# Power_Supply.net
KiCad netlist of a schematic drawn in Altium Designer
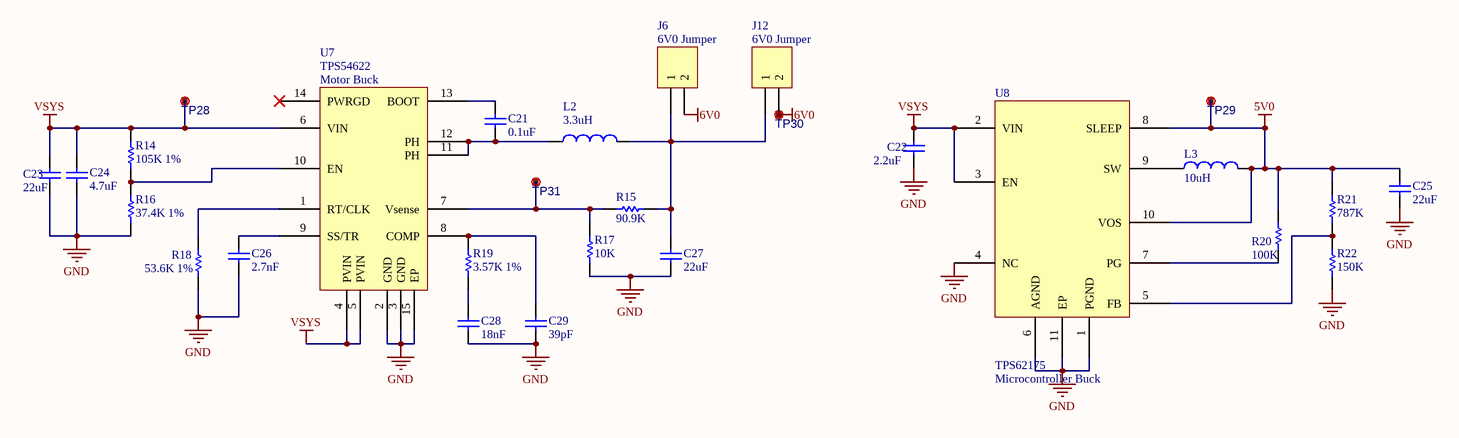
[diagram p0: Power_Supply.SchDoc]

(export (version "E")
  (design (tool "Eeschema 10.0.6"))
  (components
    (comp (ref "C21")
      (value "0.1uF")
      (footprint "CAPC0805(2012)145_N")
      (description "CAP CER 0.1UF 25V X7R 0805")
      (fields (field (name "TOLERANCE") "Â±10%"))
      (libsource (lib "Altium Content Vault") (part "CMP-1036-04410-1"))
    )
    (comp (ref "C22")
      (value "2.2uF")
      (footprint "CAPC0603(1608)100_N")
      (description "CAP CER 2.2UF 16V X5R 0603")
      (fields (field (name "TOLERANCE") "Â±10%"))
      (libsource (lib "Altium Content Vault") (part "CMP-1035-02763-1"))
    )
    (comp (ref "C23")
      (value "22uF")
      (footprint "CAPC1206(3216)190_N")
      (description "CAP CER 22UF 16V X5R 1206")
      (fields (field (name "TOLERANCE") "Â±20%"))
      (libsource (lib "Altium Content Vault") (part "CMP-1037-04993-1"))
    )
    (comp (ref "C24")
      (value "4.7uF")
      (footprint "CAPC0805(2012)145_N")
      (description "CAP CER 4.7UF 25V X5R 0805")
      (fields (field (name "TOLERANCE") "Â±10%"))
      (libsource (lib "Altium Content Vault") (part "CMP-1036-04895-1"))
    )
    (comp (ref "C25")
      (value "22uF")
      (footprint "CAPC0805(2012)145_N")
      (description "CAP CER 22UF 6.3V X5R 0805")
      (fields (field (name "TOLERANCE") "Â±20%"))
      (libsource (lib "Altium Content Vault") (part "CMP-1036-04939-1"))
    )
    (comp (ref "C26")
      (value "2.7nF")
      (footprint "CAPC0805(2012)145_N")
      (description "CAP CER 2700PF 50V X7R 0805")
      (fields (field (name "TOLERANCE") "Â±10%"))
      (libsource (lib "Altium Content Vault") (part "CMP-1036-03344-1"))
    )
    (comp (ref "C27")
      (value "22uF")
      (footprint "CAPC1206(3216)190_N")
      (description "CAP CER 22UF 10V X5R 1206")
      (fields (field (name "TOLERANCE") "Â±10%"))
      (libsource (lib "Altium Content Vault") (part "CMP-1037-04989-1"))
    )
    (comp (ref "C28")
      (value "18nF")
      (footprint "CAPC0805(2012)145_N")
      (description "CAP CER 0.018UF 50V X7R 0805")
      (fields (field (name "TOLERANCE") "Â±10%"))
      (libsource (lib "Altium Content Vault") (part "CMP-1036-04012-1"))
    )
    (comp (ref "C29")
      (value "39pF")
      (footprint "CAPC0805(2012)100_N")
      (description "CAP CER 39PF 50V NPO 0805")
      (fields (field (name "TOLERANCE") "Â±5%"))
      (libsource (lib "Altium Content Vault") (part "CMP-1036-01521-1"))
    )
    (comp (ref "J6")
      (value "6V0 Jumper")
      (footprint "HDR1X2")
      (description "PEC02SAAN")
      (fields (field (name "PUBLISHER") "Altium Limited"))
      (libsource (lib "Miscellaneous Connectors") (part "Header 2"))
    )
    (comp (ref "J12")
      (value "6V0 Jumper")
      (footprint "HDR1X2")
      (description "PEC02SAAN")
      (fields (field (name "PUBLISHER") "Altium Limited"))
      (libsource (lib "Miscellaneous Connectors") (part "Header 2"))
    )
    (comp (ref "L2")
      (value "3.3uH")
      (footprint "INDM7265X40N")
      (description "FIXED IND 3.3UH 6.5A 23 MOHM SMD")
      (fields (field (name "PUBLISHER") "Altium Limited"))
      (libsource (lib "Miscellaneous Devices") (part "Inductor"))
    )
    (comp (ref "L3")
      (value "10uH")
      (footprint "SDR0503")
      (description "FIXED IND 10UH 1.3A 130 MOHM SMD")
      (fields (field (name "PUBLISHER") "Altium Limited"))
      (libsource (lib "Miscellaneous Devices") (part "Inductor"))
    )
    (comp (ref "R14")
      (value "105K 1%")
      (footprint "RESC0402(1005)_N")
      (description "RES SMD 105K OHM 1% 1/16W 0402")
      (fields (field (name "POWER") "0.063 W") (field (name "TOLERANCE") "1%"))
      (libsource (lib "Altium Content Vault") (part "CMP-1011-00122-1"))
    )
    (comp (ref "R15")
      (value "90.9K")
      (footprint "RESC0402(1005)_N")
      (description "RES SMD 90.9K OHM 1% 1/16W 0402")
      (fields (field (name "TOLERANCE") "1 %") (field (name "POWER") "0.063 W"))
      (libsource (lib "Altium Content Vault") (part "CMP-1011-00731-1"))
    )
    (comp (ref "R16")
      (value "37.4K 1%")
      (footprint "RESC0402(1005)_N")
      (description "RES SMD 37.4K OHM 1% 1/16W 0402")
      (fields (field (name "POWER") "0.063 W") (field (name "TOLERANCE") "1%"))
      (libsource (lib "Altium Content Vault") (part "CMP-1011-00111-1"))
    )
    (comp (ref "R17")
      (value "10K")
      (footprint "RESC0402(1005)_N")
      (description "RES SMD 10K OHM 1% 1/16W 0402")
      (fields (field (name "TOLERANCE") "1 %") (field (name "POWER") "0.063 W"))
      (libsource (lib "Altium Content Vault") (part "CMP-1011-00623-1"))
    )
    (comp (ref "R18")
      (value "53.6K 1%")
      (footprint "RESC0402(1005)_N")
      (description "RES SMD 53.6K OHM 1% 1/16W 0402")
      (fields (field (name "POWER") "0.063 W") (field (name "TOLERANCE") "1%"))
      (libsource (lib "Altium Content Vault") (part "CMP-1011-00111-1"))
    )
    (comp (ref "R19")
      (value "3.57K 1%")
      (footprint "RESC0402(1005)_N")
      (description "RES SMD 3.57K OHM 1% 1/16W 0402")
      (fields (field (name "POWER") "0.063 W") (field (name "TOLERANCE") "1 %"))
      (libsource (lib "Altium Content Vault") (part "CMP-1011-00571-1"))
    )
    (comp (ref "R20")
      (value "100K")
      (footprint "RESC0402(1005)_N")
      (description "RES SMD 100K OHM 1% 1/16W 0402")
      (fields (field (name "POWER") "0.063 W") (field (name "TOLERANCE") "1 %"))
      (libsource (lib "Altium Content Vault") (part "CMP-1011-00122-1"))
    )
    (comp (ref "R21")
      (value "787K")
      (footprint "RESC0603(1608)_N")
      (description "RES SMD 787K OHM 1% 1/10W 0603")
      (fields (field (name "POWER") "0.1 W") (field (name "TOLERANCE") "1 %"))
      (libsource (lib "Altium Content Vault") (part "CMP-1012-00247-1"))
    )
    (comp (ref "R22")
      (value "150K")
      (footprint "RESC0603(1608)_N")
      (description "RES SMD 150K OHM 1% 1/10W 0603")
      (fields (field (name "POWER") "0.1 W") (field (name "TOLERANCE") "0.1 %"))
      (libsource (lib "Altium Content Vault") (part "CMP-1012-00247-1"))
    )
    (comp (ref "TP28")
      (value "Test Point")
      (footprint "Testpoint_70")
      (description "Test Pad")
      (libsource (lib "Prosthetic Hand Schematic Lib") (part "Test Point"))
    )
    (comp (ref "TP29")
      (value "Test Point")
      (footprint "Testpoint_70")
      (description "Test Pad")
      (libsource (lib "Prosthetic Hand Schematic Lib") (part "Test Point"))
    )
    (comp (ref "TP30")
      (value "Test Point")
      (footprint "Testpoint_70")
      (description "Test Pad")
      (libsource (lib "Prosthetic Hand Schematic Lib") (part "Test Point"))
    )
    (comp (ref "TP31")
      (value "Test Point")
      (footprint "Testpoint_70")
      (description "Test Pad")
      (libsource (lib "Prosthetic Hand Schematic Lib") (part "Test Point"))
    )
    (comp (ref "U7")
      (value "TPS54622")
      (footprint "S-PVQFN-N14")
      (description "IC REG BUCK ADJ 6A SYNC 14QFN")
      (fields (field (name "DESC") "Motor Buck"))
      (libsource (lib "Prosthetic Hand Schematic Lib") (part "TPS54622"))
    )
    (comp (ref "U8")
      (value "TPS62175")
      (footprint "R-PWSON-N10")
      (description "IC REG BUCK BST 5V 0.8A 10WSON")
      (fields (field (name "DESC") "Microcontroller Buck"))
      (libsource (lib "Prosthetic Hand Schematic Lib") (part "TPS62175"))
    )
  )
  (nets
    (net (code "1") (name "5V0") (class "Default")
      (node (ref "C25") (pin "2") (pinfunction "2_2") (pintype "passive"))
      (node (ref "L3") (pin "2") (pinfunction "2_2") (pintype "passive"))
      (node (ref "R20") (pin "2") (pinfunction "2_2") (pintype "passive"))
      (node (ref "R21") (pin "1") (pinfunction "1_1") (pintype "passive"))
      (node (ref "TP29") (pin "1") (pinfunction "M80_1") (pintype "passive"))
      (node (ref "U8") (pin "10") (pinfunction "VOS_10") (pintype "passive"))
      (node (ref "U8") (pin "8") (pinfunction "SLEEP_8") (pintype "passive"))
    )
    (net (code "2") (name "6V0") (class "Default")
      (node (ref "J12") (pin "2") (pinfunction "2_2") (pintype "passive"))
      (node (ref "J6") (pin "2") (pinfunction "2_2") (pintype "passive"))
      (node (ref "TP30") (pin "1") (pinfunction "M80_1") (pintype "passive"))
    )
    (net (code "3") (name "GND") (class "Default")
      (node (ref "C22") (pin "1") (pinfunction "1_1") (pintype "passive"))
      (node (ref "C23") (pin "1") (pinfunction "1_1") (pintype "passive"))
      (node (ref "C24") (pin "1") (pinfunction "1_1") (pintype "passive"))
      (node (ref "C25") (pin "1") (pinfunction "1_1") (pintype "passive"))
      (node (ref "C26") (pin "1") (pinfunction "1_1") (pintype "passive"))
      (node (ref "C27") (pin "1") (pinfunction "1_1") (pintype "passive"))
      (node (ref "C28") (pin "1") (pinfunction "1_1") (pintype "passive"))
      (node (ref "C29") (pin "1") (pinfunction "1_1") (pintype "passive"))
      (node (ref "R16") (pin "1") (pinfunction "1_1") (pintype "passive"))
      (node (ref "R17") (pin "1") (pinfunction "1_1") (pintype "passive"))
      (node (ref "R18") (pin "1") (pinfunction "1_1") (pintype "passive"))
      (node (ref "R22") (pin "1") (pinfunction "1_1") (pintype "passive"))
      (node (ref "U7") (pin "15") (pinfunction "EP_15") (pintype "passive"))
      (node (ref "U7") (pin "2") (pinfunction "GND_2") (pintype "passive"))
      (node (ref "U7") (pin "3") (pinfunction "GND_3") (pintype "passive"))
      (node (ref "U8") (pin "1") (pinfunction "PGND_1") (pintype "passive"))
      (node (ref "U8") (pin "11") (pinfunction "EP_11") (pintype "passive"))
      (node (ref "U8") (pin "4") (pinfunction "NC_4") (pintype "passive"))
      (node (ref "U8") (pin "6") (pinfunction "AGND_6") (pintype "passive"))
    )
    (net (code "4") (name "Net-(C21-Pad1)") (class "Default")
      (node (ref "C21") (pin "1") (pinfunction "1_1") (pintype "passive"))
      (node (ref "L2") (pin "1") (pinfunction "1_1") (pintype "passive"))
      (node (ref "U7") (pin "11") (pinfunction "PH_11") (pintype "passive"))
      (node (ref "U7") (pin "12") (pinfunction "PH_12") (pintype "passive"))
    )
    (net (code "5") (name "Net-(C27-Pad2)") (class "Default")
      (node (ref "C27") (pin "2") (pinfunction "2_2") (pintype "passive"))
      (node (ref "J12") (pin "1") (pinfunction "1_1") (pintype "passive"))
      (node (ref "J6") (pin "1") (pinfunction "1_1") (pintype "passive"))
      (node (ref "L2") (pin "2") (pinfunction "2_2") (pintype "passive"))
      (node (ref "R15") (pin "2") (pinfunction "2_2") (pintype "passive"))
    )
    (net (code "6") (name "Net-(C28-Pad2)") (class "Default")
      (node (ref "C28") (pin "2") (pinfunction "2_2") (pintype "passive"))
      (node (ref "R19") (pin "1") (pinfunction "1_1") (pintype "passive"))
    )
    (net (code "7") (name "Net-(TP31-M80)") (class "Default")
      (node (ref "R15") (pin "1") (pinfunction "1_1") (pintype "passive"))
      (node (ref "R17") (pin "2") (pinfunction "2_2") (pintype "passive"))
      (node (ref "TP31") (pin "1") (pinfunction "M80_1") (pintype "passive"))
      (node (ref "U7") (pin "7") (pinfunction "Vsense_7") (pintype "passive"))
    )
    (net (code "8") (name "Net-(U7-BOOT)") (class "Default")
      (node (ref "C21") (pin "2") (pinfunction "2_2") (pintype "passive"))
      (node (ref "U7") (pin "13") (pinfunction "BOOT_13") (pintype "passive"))
    )
    (net (code "9") (name "Net-(U7-COMP)") (class "Default")
      (node (ref "C29") (pin "2") (pinfunction "2_2") (pintype "passive"))
      (node (ref "R19") (pin "2") (pinfunction "2_2") (pintype "passive"))
      (node (ref "U7") (pin "8") (pinfunction "COMP_8") (pintype "passive"))
    )
    (net (code "10") (name "Net-(U7-EN)") (class "Default")
      (node (ref "R14") (pin "2") (pinfunction "2_2") (pintype "passive"))
      (node (ref "R16") (pin "2") (pinfunction "2_2") (pintype "passive"))
      (node (ref "U7") (pin "10") (pinfunction "EN_10") (pintype "passive"))
    )
    (net (code "11") (name "Net-(U7-RT{slash}CLK)") (class "Default")
      (node (ref "R18") (pin "2") (pinfunction "2_2") (pintype "passive"))
      (node (ref "U7") (pin "1") (pinfunction "RT/CLK_1") (pintype "passive"))
    )
    (net (code "12") (name "Net-(U7-SS{slash}TR)") (class "Default")
      (node (ref "C26") (pin "2") (pinfunction "2_2") (pintype "passive"))
      (node (ref "U7") (pin "9") (pinfunction "SS/TR_9") (pintype "passive"))
    )
    (net (code "13") (name "Net-(U8-FB)") (class "Default")
      (node (ref "R21") (pin "2") (pinfunction "2_2") (pintype "passive"))
      (node (ref "R22") (pin "2") (pinfunction "2_2") (pintype "passive"))
      (node (ref "U8") (pin "5") (pinfunction "FB_5") (pintype "passive"))
    )
    (net (code "14") (name "Net-(U8-PG)") (class "Default")
      (node (ref "R20") (pin "1") (pinfunction "1_1") (pintype "passive"))
      (node (ref "U8") (pin "7") (pinfunction "PG_7") (pintype "passive"))
    )
    (net (code "15") (name "Net-(U8-SW)") (class "Default")
      (node (ref "L3") (pin "1") (pinfunction "1_1") (pintype "passive"))
      (node (ref "U8") (pin "9") (pinfunction "SW_9") (pintype "passive"))
    )
    (net (code "16") (name "VSYS") (class "Default")
      (node (ref "C22") (pin "2") (pinfunction "2_2") (pintype "passive"))
      (node (ref "C23") (pin "2") (pinfunction "2_2") (pintype "passive"))
      (node (ref "C24") (pin "2") (pinfunction "2_2") (pintype "passive"))
      (node (ref "R14") (pin "1") (pinfunction "1_1") (pintype "passive"))
      (node (ref "TP28") (pin "1") (pinfunction "M80_1") (pintype "passive"))
      (node (ref "U7") (pin "4") (pinfunction "PVIN_4") (pintype "passive"))
      (node (ref "U7") (pin "5") (pinfunction "PVIN_5") (pintype "passive"))
      (node (ref "U7") (pin "6") (pinfunction "VIN_6") (pintype "passive"))
      (node (ref "U8") (pin "2") (pinfunction "VIN_2") (pintype "passive"))
      (node (ref "U8") (pin "3") (pinfunction "EN_3") (pintype "passive"))
    )
    (net (code "17") (name "unconnected-(U7-PWRGD-Pad14)") (class "Default")
      (node (ref "U7") (pin "14") (pinfunction "PWRGD_14") (pintype "passive+no_connect"))
    )
  )
)
